# connecteurs.net
KiCad netlist of a schematic drawn in Altium Designer
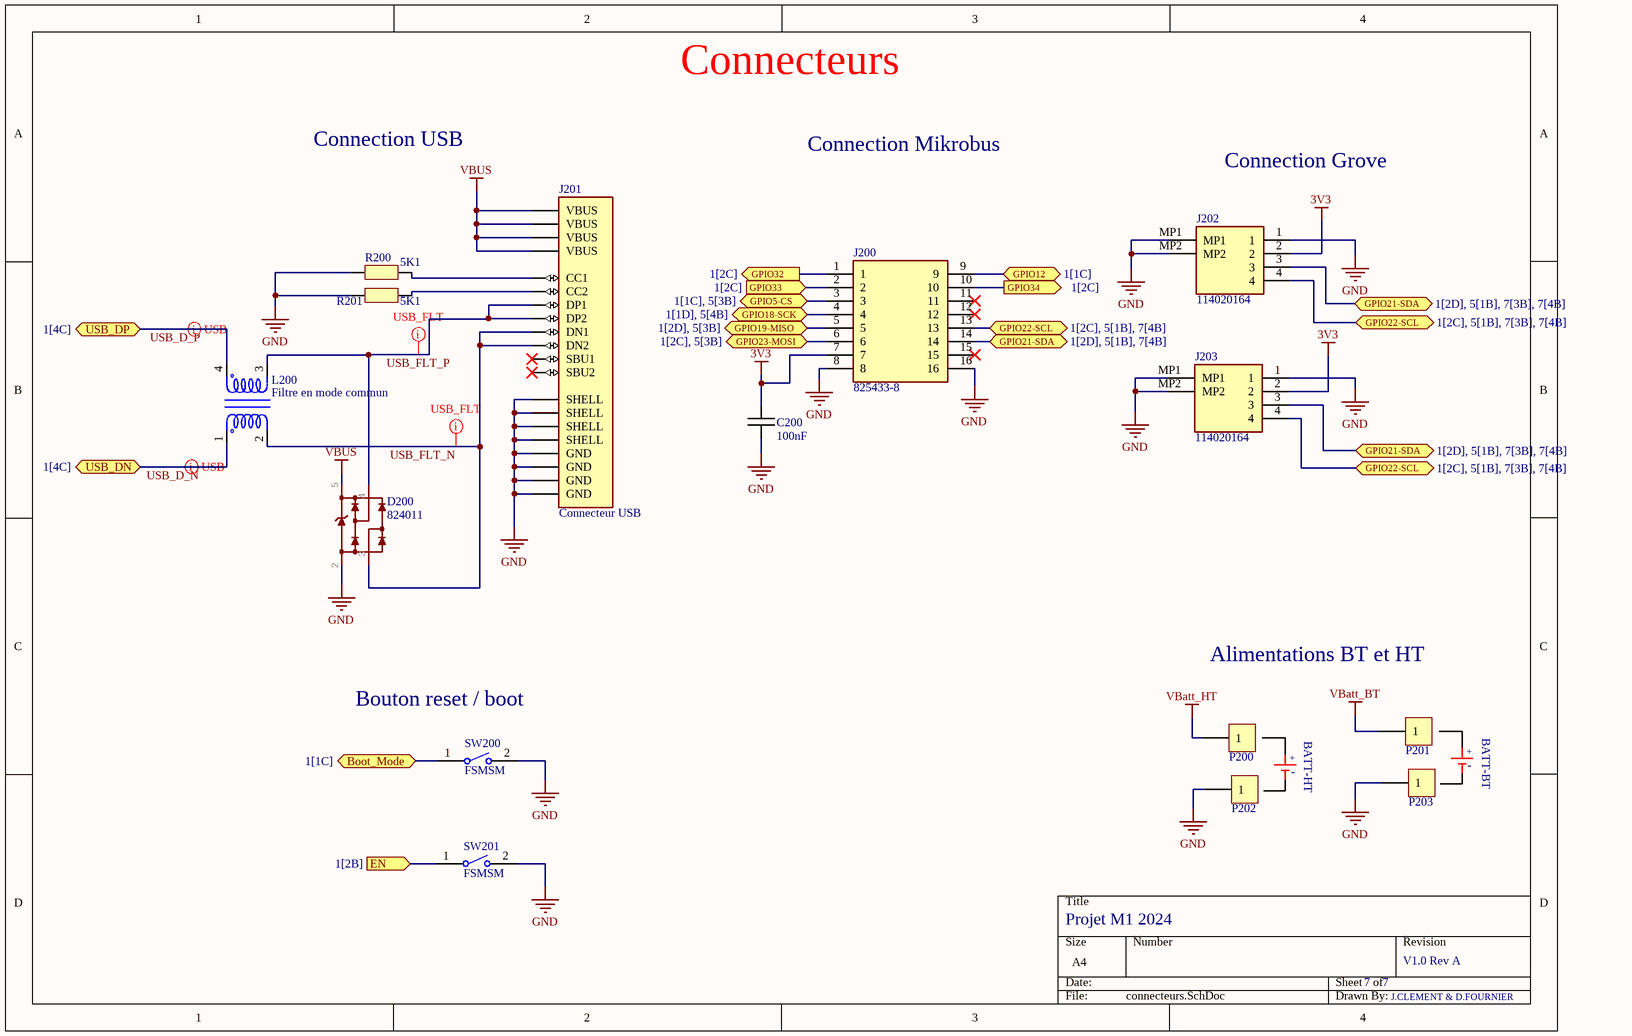
[diagram p0: connecteurs.SchDoc]

(export (version "E")
  (design (tool "Eeschema 10.0.6"))
  (components
    (comp (ref "C200")
      (value "100nF")
      (footprint "CAPA_0603")
      (libsource (lib "SCHLibrary") (part "Capacitor"))
    )
    (comp (ref "D200") (value "824011") (footprint "SOT23-5") (libsource (lib "SCHLibrary") (part "824011")))
    (comp (ref "J200")
      (value "825433-8")
      (footprint "Connect-Mikrobus")
      (description "Headers & Wire Housings 8P double for connection mikrobus")
      (fields (field (name "MOUSER PART NUMBER") "571-825433-8"))
      (libsource (lib "SCHLibrary") (part "Connect-Mikrobus"))
    )
    (comp (ref "J201")
      (value "Connecteur USB")
      (footprint "USB4085-GF-A")
      (description "Connecteurs USB USB Type C, 2.0, Rec, TH , G/F, RA , Top Mnt, T & R")
      (libsource (lib "SCHLibrary") (part "USB4085-GF-A"))
    )
    (comp (ref "J202")
      (value "114020164")
      (footprint "114020164")
      (description "Seeed Studio Accessories Grove Female Header - SMD-4P-2.0mm-90D-20Pcs")
      (fields (field (name "MOUSER PART NUMBER") "713-114020164"))
      (libsource (lib "SCHLibrary") (part "114020164"))
    )
    (comp (ref "J203")
      (value "114020164")
      (footprint "114020164")
      (description "Seeed Studio Accessories Grove Female Header - SMD-4P-2.0mm-90D-20Pcs")
      (fields (field (name "MOUSER PART NUMBER") "713-114020164"))
      (libsource (lib "SCHLibrary") (part "114020164"))
    )
    (comp (ref "L200")
      (value "Filtre en mode commun")
      (footprint "WE-CNSW-1206")
      (description "Bobines / filtres en mode commun WE-CNSW 1206 370mA 90Ohm 100MHz AECQ200")
      (libsource (lib "SCHLibrary") (part "744232090"))
    )
    (comp (ref "P200")
      (value "Plage CMS 10x5")
      (footprint "Plage CMS 10x5")
      (description "Plage de report CMS 10x5mm")
      (libsource (lib "SCHLibrary") (part "Plage CMS 10x5_1"))
    )
    (comp (ref "P201")
      (value "Plage CMS 10x5")
      (footprint "Plage CMS 10x5")
      (description "Plage de report CMS 10x5mm")
      (libsource (lib "SCHLibrary") (part "Plage CMS 10x5_1"))
    )
    (comp (ref "P202")
      (value "Plage CMS 10x5")
      (footprint "Plage CMS 10x5")
      (description "Plage de report CMS 10x5mm")
      (libsource (lib "SCHLibrary") (part "Plage CMS 10x5_1"))
    )
    (comp (ref "P203")
      (value "Plage CMS 10x5")
      (footprint "Plage CMS 10x5")
      (description "Plage de report CMS 10x5mm")
      (libsource (lib "SCHLibrary") (part "Plage CMS 10x5_1"))
    )
    (comp (ref "R200") (value "5K1") (footprint "RES_0603") (libsource (lib "SCHLibrary") (part "Resistor")))
    (comp (ref "R201") (value "5K1") (footprint "RES_0603") (libsource (lib "SCHLibrary") (part "Resistor")))
    (comp (ref "SW200")
      (value "FSMSM")
      (footprint "TECO-FSMSM-2_V")
      (description "FSMSM Push Button Switch, 50 mA, -35 to 85 degC, 2-Pin SMD, RoHS, Bulk")
      (fields (field (name "MANUFACTURER") "TE Connectivity"))
      (libsource (lib "SCHLibrary") (part "CMP-2000-07511-1"))
    )
    (comp (ref "SW201")
      (value "FSMSM")
      (footprint "TECO-FSMSM-2_V")
      (description "FSMSM Push Button Switch, 50 mA, -35 to 85 degC, 2-Pin SMD, RoHS, Bulk")
      (fields (field (name "MANUFACTURER") "TE Connectivity"))
      (libsource (lib "SCHLibrary") (part "CMP-2000-07511-1"))
    )
  )
  (nets
    (net (code "1") (name "/Boot_Mode") (class "Default")
      (node (ref "SW200") (pin "1") (pinfunction "1_1") (pintype "passive"))
    )
    (net (code "2") (name "/EN") (class "Default")
      (node (ref "SW201") (pin "1") (pinfunction "1_1") (pintype "passive"))
    )
    (net (code "3") (name "/GPIO5-CS") (class "Default")
      (node (ref "J200") (pin "3") (pinfunction "3_3") (pintype "passive"))
    )
    (net (code "4") (name "/GPIO12") (class "Default")
      (node (ref "J200") (pin "9") (pinfunction "9_9") (pintype "passive"))
    )
    (net (code "5") (name "/GPIO18-SCK") (class "Default")
      (node (ref "J200") (pin "4") (pinfunction "4_4") (pintype "passive"))
    )
    (net (code "6") (name "/GPIO19-MISO") (class "Default")
      (node (ref "J200") (pin "5") (pinfunction "5_5") (pintype "passive"))
    )
    (net (code "7") (name "/GPIO21-SDA") (class "Default")
      (node (ref "J200") (pin "14") (pinfunction "14_14") (pintype "passive"))
      (node (ref "J202") (pin "3") (pinfunction "3_3") (pintype "passive"))
      (node (ref "J203") (pin "3") (pinfunction "3_3") (pintype "passive"))
    )
    (net (code "8") (name "/GPIO22-SCL") (class "Default")
      (node (ref "J200") (pin "13") (pinfunction "13_13") (pintype "passive"))
      (node (ref "J202") (pin "4") (pinfunction "4_4") (pintype "passive"))
      (node (ref "J203") (pin "4") (pinfunction "4_4") (pintype "passive"))
    )
    (net (code "9") (name "/GPIO23-MOSI") (class "Default")
      (node (ref "J200") (pin "6") (pinfunction "6_6") (pintype "passive"))
    )
    (net (code "10") (name "/GPIO32") (class "Default")
      (node (ref "J200") (pin "1") (pinfunction "1_1") (pintype "passive"))
    )
    (net (code "11") (name "/GPIO33") (class "Default")
      (node (ref "J200") (pin "2") (pinfunction "2_2") (pintype "passive"))
    )
    (net (code "12") (name "/GPIO34") (class "Default")
      (node (ref "J200") (pin "10") (pinfunction "10_10") (pintype "passive"))
    )
    (net (code "13") (name "/USB_D_N") (class "Default")
      (node (ref "L200") (pin "1") (pinfunction "1_1") (pintype "passive"))
    )
    (net (code "14") (name "/USB_D_P") (class "Default")
      (node (ref "L200") (pin "4") (pinfunction "4_4") (pintype "passive"))
    )
    (net (code "15") (name "/USB_FLT_N") (class "Default")
      (node (ref "D200") (pin "3") (pinfunction "1_3") (pintype "passive"))
      (node (ref "J201") (pin "A7") (pinfunction "DN1_A7") (pintype "bidirectional"))
      (node (ref "J201") (pin "B7") (pinfunction "DN2_B7") (pintype "bidirectional"))
      (node (ref "L200") (pin "2") (pinfunction "2_2") (pintype "passive"))
    )
    (net (code "16") (name "/USB_FLT_P") (class "Default")
      (node (ref "D200") (pin "4") (pinfunction "2_4") (pintype "passive"))
      (node (ref "J201") (pin "A6") (pinfunction "DP1_A6") (pintype "bidirectional"))
      (node (ref "J201") (pin "B6") (pinfunction "DP2_B6") (pintype "bidirectional"))
      (node (ref "L200") (pin "3") (pinfunction "3_3") (pintype "passive"))
    )
    (net (code "17") (name "3V3") (class "Default")
      (node (ref "C200") (pin "1") (pinfunction "1_1") (pintype "passive"))
      (node (ref "J200") (pin "7") (pinfunction "7_7") (pintype "passive"))
      (node (ref "J202") (pin "2") (pinfunction "2_2") (pintype "passive"))
      (node (ref "J203") (pin "2") (pinfunction "2_2") (pintype "passive"))
    )
    (net (code "18") (name "GND") (class "Default")
      (node (ref "C200") (pin "2") (pinfunction "2_2") (pintype "passive"))
      (node (ref "D200") (pin "2") (pinfunction "GND_2") (pintype "power_in"))
      (node (ref "J200") (pin "16") (pinfunction "16_16") (pintype "passive"))
      (node (ref "J200") (pin "8") (pinfunction "8_8") (pintype "passive"))
      (node (ref "J201") (pin "A1") (pinfunction "GND_A1") (pintype "power_in"))
      (node (ref "J201") (pin "A12") (pinfunction "GND_A12") (pintype "power_in"))
      (node (ref "J201") (pin "B1") (pinfunction "GND_B1") (pintype "power_in"))
      (node (ref "J201") (pin "B12") (pinfunction "GND_B12") (pintype "power_in"))
      (node (ref "J201") (pin "S1") (pinfunction "SHELL_S1") (pintype "passive"))
      (node (ref "J201") (pin "S2") (pinfunction "SHELL_S2") (pintype "passive"))
      (node (ref "J201") (pin "S3") (pinfunction "SHELL_S3") (pintype "passive"))
      (node (ref "J201") (pin "S4") (pinfunction "SHELL_S4") (pintype "passive"))
      (node (ref "J202") (pin "1") (pinfunction "1_1") (pintype "passive"))
      (node (ref "J202") (pin "MP1") (pinfunction "MP1_MP1") (pintype "passive"))
      (node (ref "J202") (pin "MP2") (pinfunction "MP2_MP2") (pintype "passive"))
      (node (ref "J203") (pin "1") (pinfunction "1_1") (pintype "passive"))
      (node (ref "J203") (pin "MP1") (pinfunction "MP1_MP1") (pintype "passive"))
      (node (ref "J203") (pin "MP2") (pinfunction "MP2_MP2") (pintype "passive"))
      (node (ref "P202") (pin "1") (pinfunction "1_1") (pintype "passive"))
      (node (ref "P203") (pin "1") (pinfunction "1_1") (pintype "passive"))
      (node (ref "R200") (pin "1") (pinfunction "1_1") (pintype "passive"))
      (node (ref "R201") (pin "1") (pinfunction "1_1") (pintype "passive"))
      (node (ref "SW200") (pin "2") (pinfunction "2_2") (pintype "passive"))
      (node (ref "SW201") (pin "2") (pinfunction "2_2") (pintype "passive"))
    )
    (net (code "19") (name "Net-(J201-CC1)") (class "Default")
      (node (ref "J201") (pin "A5") (pinfunction "CC1_A5") (pintype "bidirectional"))
      (node (ref "R200") (pin "2") (pinfunction "2_2") (pintype "passive"))
    )
    (net (code "20") (name "Net-(J201-CC2)") (class "Default")
      (node (ref "J201") (pin "B5") (pinfunction "CC2_B5") (pintype "bidirectional"))
      (node (ref "R201") (pin "2") (pinfunction "2_2") (pintype "passive"))
    )
    (net (code "21") (name "VBUS") (class "Default")
      (node (ref "D200") (pin "5") (pinfunction "VDD_5") (pintype "power_in"))
      (node (ref "J201") (pin "A4") (pinfunction "VBUS_A4") (pintype "power_in"))
      (node (ref "J201") (pin "A9") (pinfunction "VBUS_A9") (pintype "power_in"))
      (node (ref "J201") (pin "B4") (pinfunction "VBUS_B4") (pintype "power_in"))
      (node (ref "J201") (pin "B9") (pinfunction "VBUS_B9") (pintype "power_in"))
    )
    (net (code "22") (name "VBatt_BT") (class "Default")
      (node (ref "P201") (pin "1") (pinfunction "1_1") (pintype "passive"))
    )
    (net (code "23") (name "VBatt_HT") (class "Default")
      (node (ref "P200") (pin "1") (pinfunction "1_1") (pintype "passive"))
    )
    (net (code "24") (name "unconnected-(J200-Pad11)") (class "Default")
      (node (ref "J200") (pin "11") (pinfunction "11_11") (pintype "passive+no_connect"))
    )
    (net (code "25") (name "unconnected-(J200-Pad12)") (class "Default")
      (node (ref "J200") (pin "12") (pinfunction "12_12") (pintype "passive+no_connect"))
    )
    (net (code "26") (name "unconnected-(J200-Pad15)") (class "Default")
      (node (ref "J200") (pin "15") (pinfunction "15_15") (pintype "passive+no_connect"))
    )
    (net (code "27") (name "unconnected-(J201-SBU1-PadA8)") (class "Default")
      (node (ref "J201") (pin "A8") (pinfunction "SBU1_A8") (pintype "bidirectional+no_connect"))
    )
    (net (code "28") (name "unconnected-(J201-SBU2-PadB8)") (class "Default")
      (node (ref "J201") (pin "B8") (pinfunction "SBU2_B8") (pintype "bidirectional+no_connect"))
    )
  )
)
